# PWR_LMQ66430.net
KiCad netlist of a schematic drawn in Altium Designer
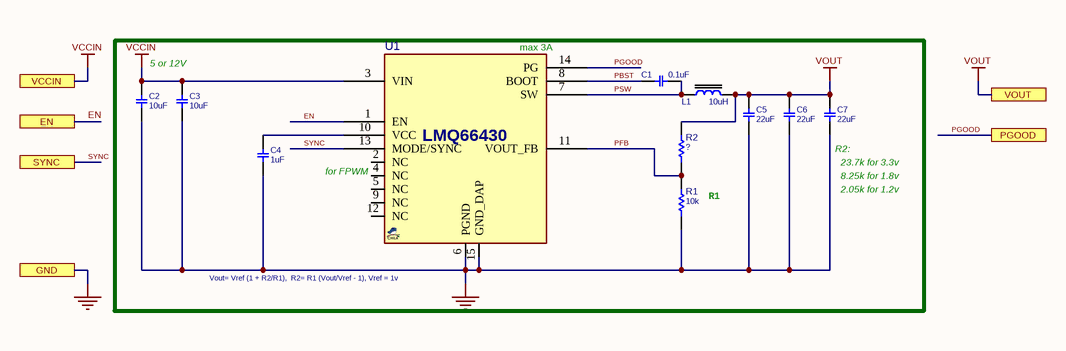
[diagram p0: PWR_LMQ66430.SchDoc]

(export (version "E")
  (design (tool "Eeschema 10.0.6"))
  (components
    (comp (ref "C1")
      (value "0.1uF")
      (footprint "C0402A")
      (description "CAP, MLCC")
      (libsource (lib "passive_mlcc_smd") (part "CAP_SMD_MLCC_100n50V"))
    )
    (comp (ref "C2")
      (value "10uF")
      (footprint "C0805")
      (description "CAP, MLCC")
      (fields (field (name "MANF_P#") "CL21A106KAYNNNE") (field (name "MANF") "Samsung"))
      (libsource (lib "passive_smd") (part "CAP_SMD_MLCC"))
    )
    (comp (ref "C3")
      (value "10uF")
      (footprint "C0805")
      (description "CAP, MLCC")
      (fields (field (name "MANF_P#") "CL21A106KAYNNNE") (field (name "MANF") "Samsung"))
      (libsource (lib "passive_smd") (part "CAP_SMD_MLCC"))
    )
    (comp (ref "C4")
      (value "1uF")
      (footprint "C0402A")
      (description "CAP, MLCC")
      (fields (field (name "MANF") "Samsung"))
      (libsource (lib "passive_smd") (part "CAP_SMD_MLCC"))
    )
    (comp (ref "C5")
      (value "22uF")
      (footprint "C0805A")
      (description "CAP, MLCC")
      (fields (field (name "MANF") "Samsung") (field (name "MANF_P#") "CL21A476MQYNNNE"))
      (libsource (lib "passive_mlcc_smd") (part "CAP_SMD_MLCC_47u25V"))
    )
    (comp (ref "C6")
      (value "22uF")
      (footprint "C0805A")
      (description "CAP, MLCC")
      (fields (field (name "MANF") "Samsung") (field (name "MANF_P#") "CL21A476MQYNNNE"))
      (libsource (lib "passive_mlcc_smd") (part "CAP_SMD_MLCC_47u25V"))
    )
    (comp (ref "C7")
      (value "22uF")
      (footprint "C0805A")
      (description "CAP, MLCC")
      (fields (field (name "MANF") "Samsung") (field (name "MANF_P#") "CL21A476MQYNNNE"))
      (libsource (lib "passive_mlcc_smd") (part "CAP_SMD_MLCC_47u25V"))
    )
    (comp (ref "L1")
      (value "10uH")
      (footprint "L_7")
      (description "INDUCTOR")
      (fields (field (name "MANF") "KYOCERA AVX") (field (name "MANF_P#") "LMLP07A7M100DTAS"))
      (libsource (lib "chila_passive") (part "IND_SMD_2.2uH_4A"))
    )
    (comp (ref "R1")
      (value "10k")
      (footprint "R0402A")
      (description "RESISTOR, SMD, 20K, 0402")
      (libsource (lib "chila_passive") (part "RES_SMD"))
    )
    (comp (ref "R2")
      (value "?")
      (footprint "R0402A")
      (description "RESISTOR, SMD, 20K, 0402")
      (libsource (lib "chila_passive") (part "RES_SMD"))
    )
    (comp (ref "U1")
      (value "LMQ66430")
      (footprint "QFN50_15_RXB")
      (description "REG, Switching, Buck, 3.6~36Vin, 3A, RXB-15")
      (fields (field (name "MANF") "Texas Instruments") (field (name "MANF_P#") "LMQ66430MC3RXBRQ1"))
      (libsource (lib "pwr_switching_buck_lowEMI") (part "VREG_LMQ66430MC3_QFN15"))
    )
  )
  (nets
    (net (code "1") (name "/EN") (class "Default")
      (node (ref "U1") (pin "1") (pinfunction "EN_1") (pintype "passive"))
    )
    (net (code "2") (name "/PBST") (class "Default")
      (node (ref "C1") (pin "1") (pinfunction "1_1") (pintype "passive"))
      (node (ref "U1") (pin "8") (pinfunction "BOOT_8") (pintype "passive"))
    )
    (net (code "3") (name "/PFB") (class "Default")
      (node (ref "R1") (pin "1") (pinfunction "1_1") (pintype "passive"))
      (node (ref "R2") (pin "2") (pinfunction "2_2") (pintype "passive"))
      (node (ref "U1") (pin "11") (pinfunction "VOUT_FB_11") (pintype "passive"))
    )
    (net (code "4") (name "/PGOOD") (class "Default")
      (node (ref "U1") (pin "14") (pinfunction "PG_14") (pintype "passive"))
    )
    (net (code "5") (name "/PSW") (class "Default")
      (node (ref "C1") (pin "2") (pinfunction "2_2") (pintype "passive"))
      (node (ref "L1") (pin "1") (pinfunction "1_1") (pintype "passive"))
      (node (ref "U1") (pin "7") (pinfunction "SW_7") (pintype "passive"))
    )
    (net (code "6") (name "/SYNC") (class "Default")
      (node (ref "U1") (pin "13") (pinfunction "MODE/SYNC_13") (pintype "passive"))
    )
    (net (code "7") (name "GND") (class "Default")
      (node (ref "C2") (pin "1") (pinfunction "1_1") (pintype "passive"))
      (node (ref "C3") (pin "1") (pinfunction "1_1") (pintype "passive"))
      (node (ref "C4") (pin "1") (pinfunction "1_1") (pintype "passive"))
      (node (ref "C5") (pin "2") (pinfunction "2_2") (pintype "passive"))
      (node (ref "C6") (pin "2") (pinfunction "2_2") (pintype "passive"))
      (node (ref "C7") (pin "2") (pinfunction "2_2") (pintype "passive"))
      (node (ref "R1") (pin "2") (pinfunction "2_2") (pintype "passive"))
      (node (ref "U1") (pin "15") (pinfunction "GND_DAP_15") (pintype "passive"))
      (node (ref "U1") (pin "6") (pinfunction "PGND_6") (pintype "passive"))
    )
    (net (code "8") (name "Net-(U1-VCC)") (class "Default")
      (node (ref "C4") (pin "2") (pinfunction "2_2") (pintype "passive"))
      (node (ref "U1") (pin "10") (pinfunction "VCC_10") (pintype "passive"))
    )
    (net (code "9") (name "VCCIN") (class "Default")
      (node (ref "C2") (pin "2") (pinfunction "2_2") (pintype "passive"))
      (node (ref "C3") (pin "2") (pinfunction "2_2") (pintype "passive"))
      (node (ref "U1") (pin "3") (pinfunction "VIN_3") (pintype "passive"))
    )
    (net (code "10") (name "VOUT") (class "Default")
      (node (ref "C5") (pin "1") (pinfunction "1_1") (pintype "passive"))
      (node (ref "C6") (pin "1") (pinfunction "1_1") (pintype "passive"))
      (node (ref "C7") (pin "1") (pinfunction "1_1") (pintype "passive"))
      (node (ref "L1") (pin "2") (pinfunction "2_2") (pintype "passive"))
      (node (ref "R2") (pin "1") (pinfunction "1_1") (pintype "passive"))
    )
    (net (code "11") (name "unconnected-(U1-NC-Pad2)") (class "Default")
      (node (ref "U1") (pin "2") (pinfunction "NC_2") (pintype "passive"))
    )
    (net (code "12") (name "unconnected-(U1-NC-Pad4)") (class "Default")
      (node (ref "U1") (pin "4") (pinfunction "NC_4") (pintype "passive"))
    )
    (net (code "13") (name "unconnected-(U1-NC-Pad5)") (class "Default")
      (node (ref "U1") (pin "5") (pinfunction "NC_5") (pintype "passive"))
    )
    (net (code "14") (name "unconnected-(U1-NC-Pad9)") (class "Default")
      (node (ref "U1") (pin "9") (pinfunction "NC_9") (pintype "passive"))
    )
    (net (code "15") (name "unconnected-(U1-NC-Pad12)") (class "Default")
      (node (ref "U1") (pin "12") (pinfunction "NC_12") (pintype "passive"))
    )
  )
)
